# light_160mm_v1_0.net
KiCad netlist of a schematic drawn in EAGLE
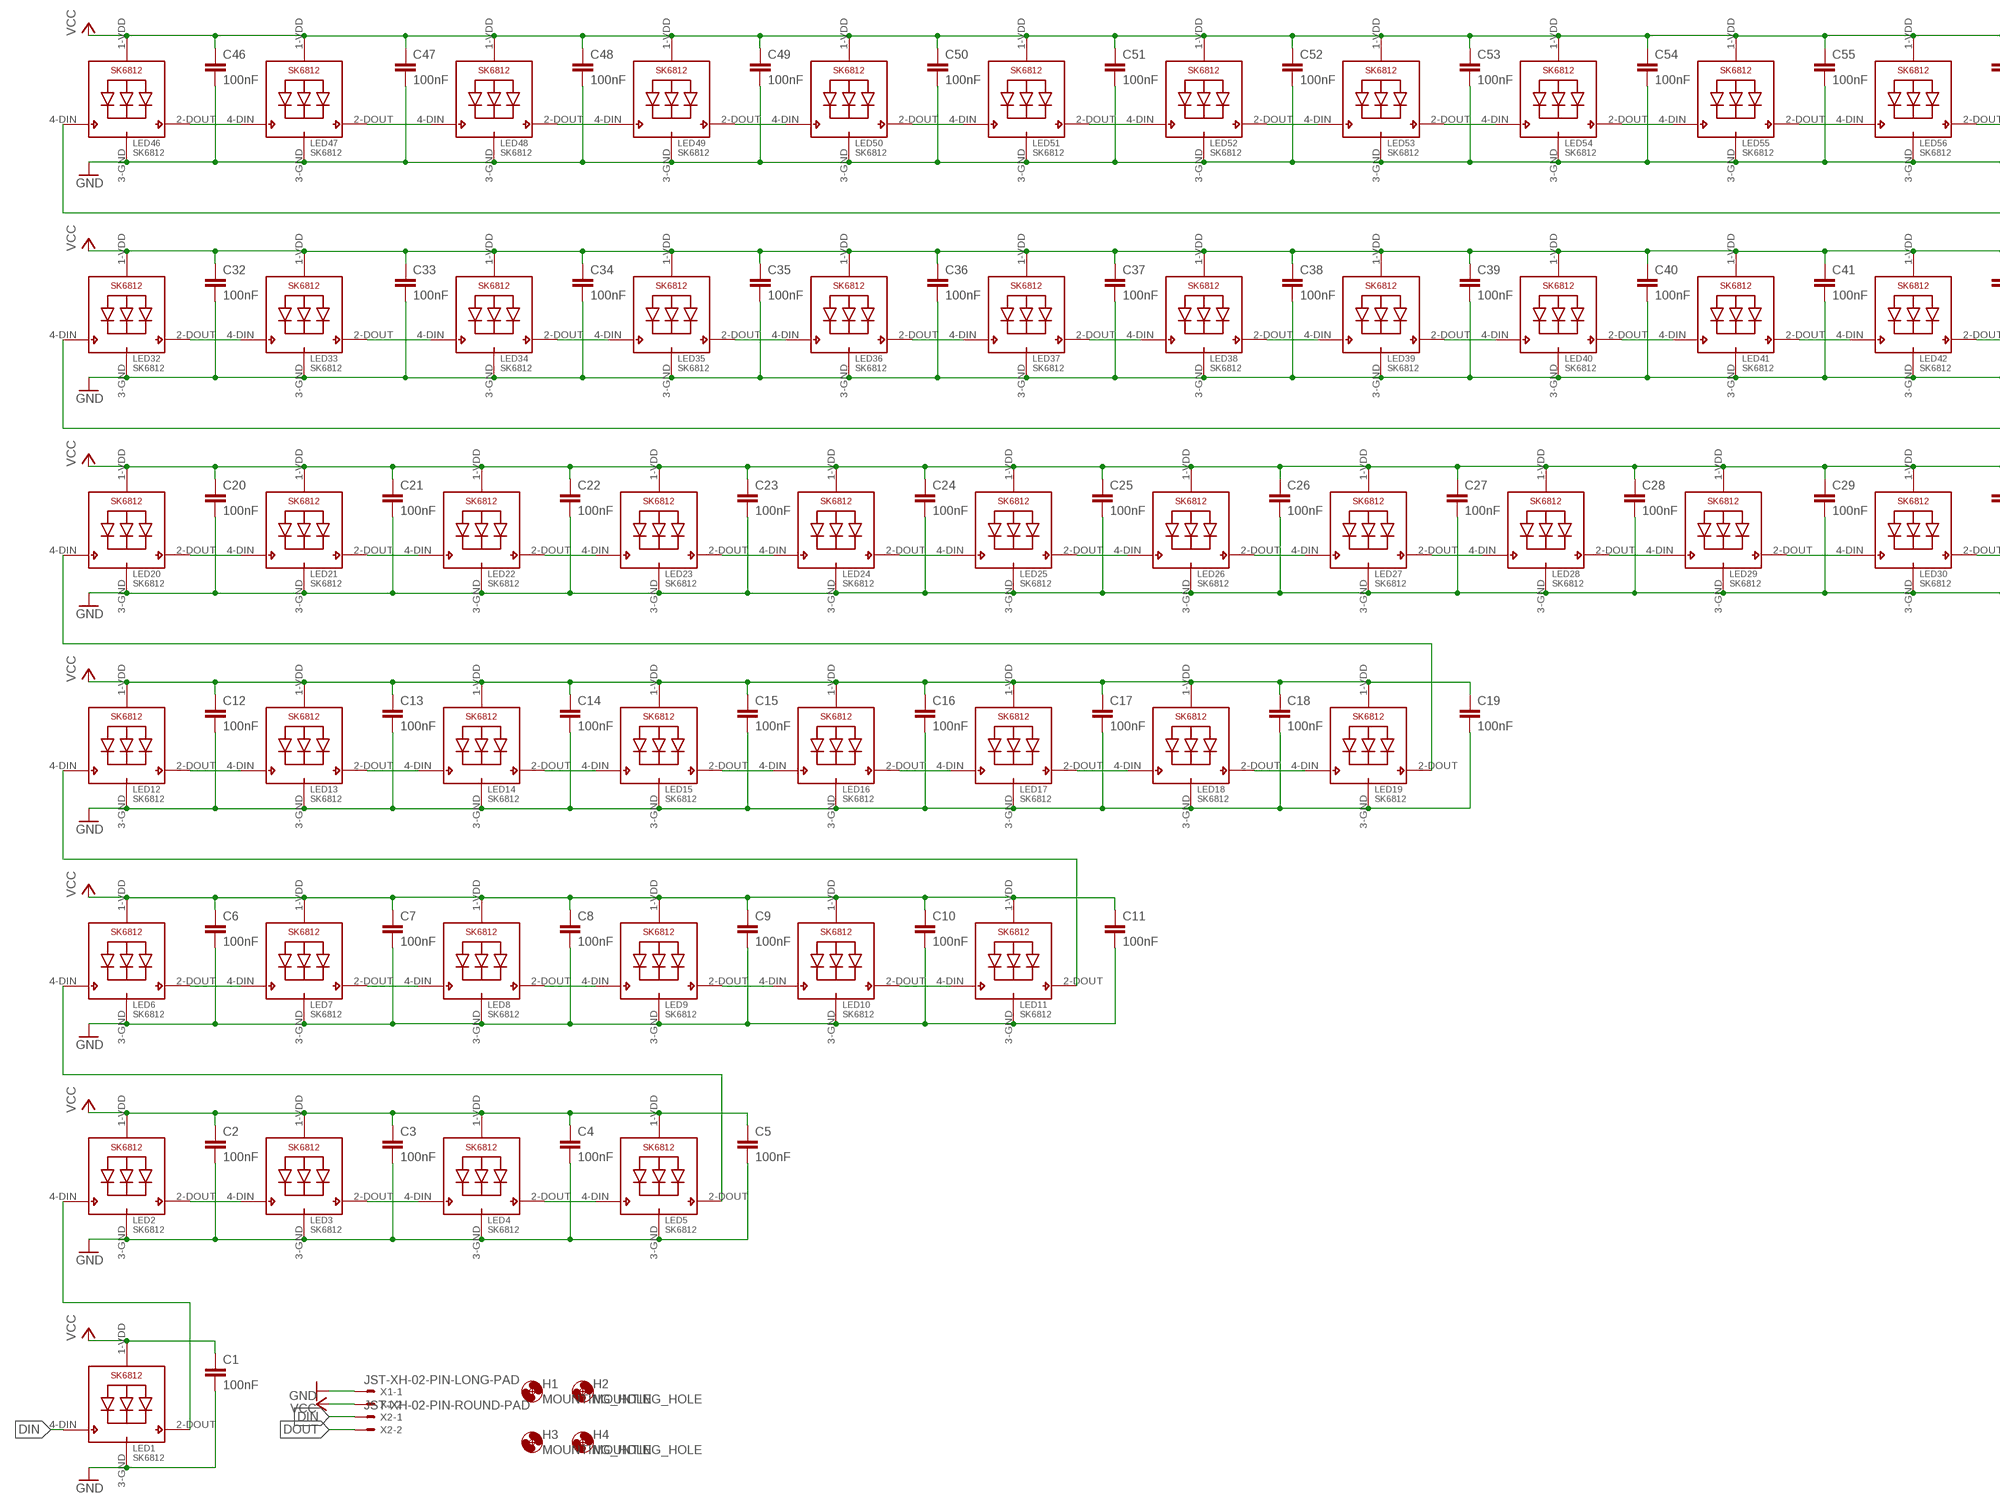
[diagram p0: schematic, sheet 1, part 1 of 2]
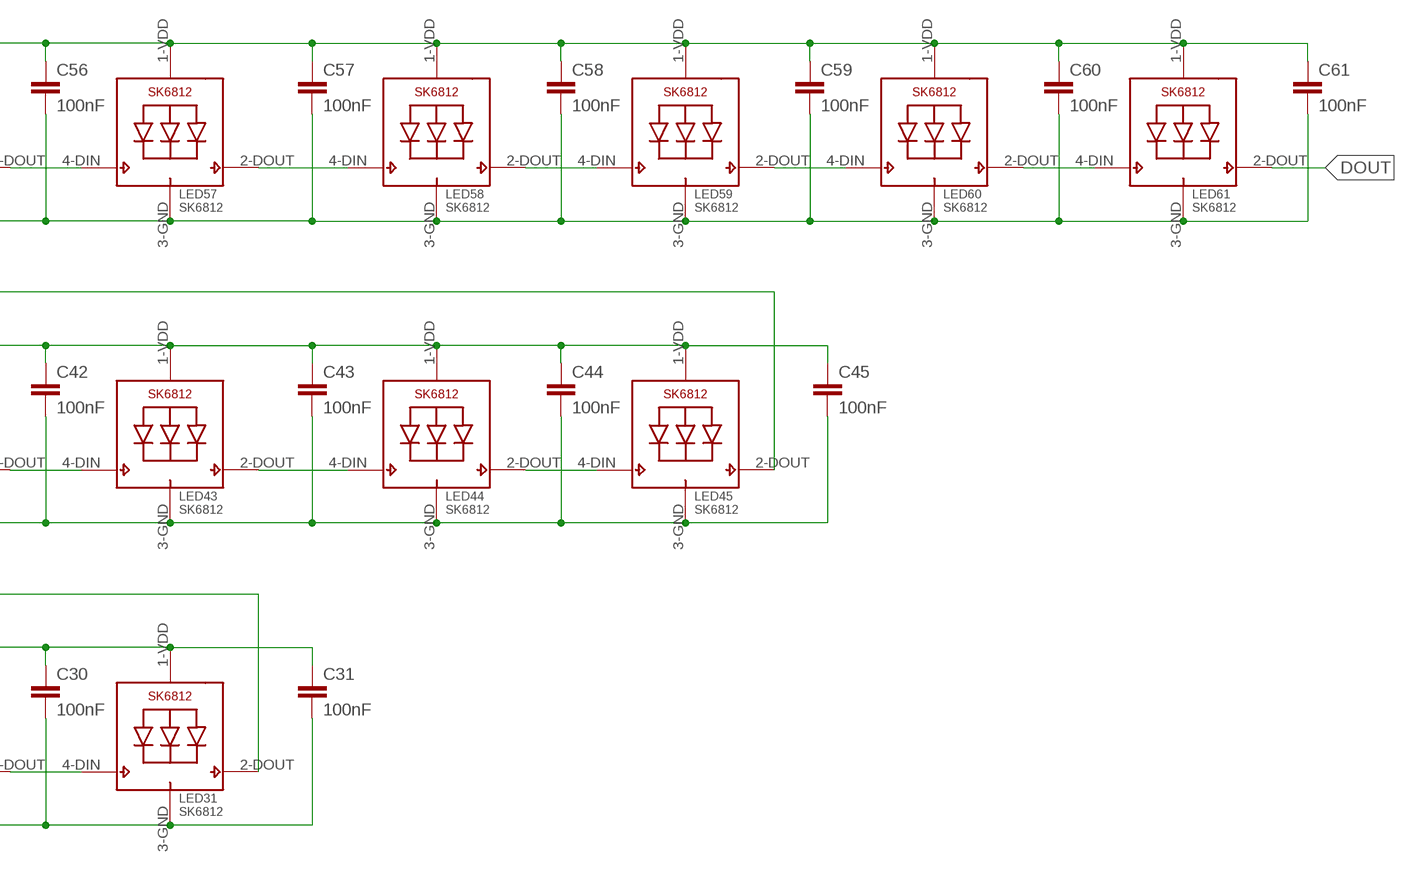
[diagram p1: schematic, sheet 1, part 2 of 2]

(export (version "E")
  (design (tool "Eeschema 10.0.6"))
  (components
    (comp (ref "C1")
      (value "100nF")
      (footprint "eagle-import:C0805")
      (libsource (lib "eagle-import") (part "C-EUC0805"))
    )
    (comp (ref "C2")
      (value "100nF")
      (footprint "eagle-import:C0805")
      (libsource (lib "eagle-import") (part "C-EUC0805"))
    )
    (comp (ref "C3")
      (value "100nF")
      (footprint "eagle-import:C0805")
      (libsource (lib "eagle-import") (part "C-EUC0805"))
    )
    (comp (ref "C4")
      (value "100nF")
      (footprint "eagle-import:C0805")
      (libsource (lib "eagle-import") (part "C-EUC0805"))
    )
    (comp (ref "C5")
      (value "100nF")
      (footprint "eagle-import:C0805")
      (libsource (lib "eagle-import") (part "C-EUC0805"))
    )
    (comp (ref "C6")
      (value "100nF")
      (footprint "eagle-import:C0805")
      (libsource (lib "eagle-import") (part "C-EUC0805"))
    )
    (comp (ref "C7")
      (value "100nF")
      (footprint "eagle-import:C0805")
      (libsource (lib "eagle-import") (part "C-EUC0805"))
    )
    (comp (ref "C8")
      (value "100nF")
      (footprint "eagle-import:C0805")
      (libsource (lib "eagle-import") (part "C-EUC0805"))
    )
    (comp (ref "C9")
      (value "100nF")
      (footprint "eagle-import:C0805")
      (libsource (lib "eagle-import") (part "C-EUC0805"))
    )
    (comp (ref "C10")
      (value "100nF")
      (footprint "eagle-import:C0805")
      (libsource (lib "eagle-import") (part "C-EUC0805"))
    )
    (comp (ref "C11")
      (value "100nF")
      (footprint "eagle-import:C0805")
      (libsource (lib "eagle-import") (part "C-EUC0805"))
    )
    (comp (ref "C12")
      (value "100nF")
      (footprint "eagle-import:C0805")
      (libsource (lib "eagle-import") (part "C-EUC0805"))
    )
    (comp (ref "C13")
      (value "100nF")
      (footprint "eagle-import:C0805")
      (libsource (lib "eagle-import") (part "C-EUC0805"))
    )
    (comp (ref "C14")
      (value "100nF")
      (footprint "eagle-import:C0805")
      (libsource (lib "eagle-import") (part "C-EUC0805"))
    )
    (comp (ref "C15")
      (value "100nF")
      (footprint "eagle-import:C0805")
      (libsource (lib "eagle-import") (part "C-EUC0805"))
    )
    (comp (ref "C16")
      (value "100nF")
      (footprint "eagle-import:C0805")
      (libsource (lib "eagle-import") (part "C-EUC0805"))
    )
    (comp (ref "C17")
      (value "100nF")
      (footprint "eagle-import:C0805")
      (libsource (lib "eagle-import") (part "C-EUC0805"))
    )
    (comp (ref "C18")
      (value "100nF")
      (footprint "eagle-import:C0805")
      (libsource (lib "eagle-import") (part "C-EUC0805"))
    )
    (comp (ref "C19")
      (value "100nF")
      (footprint "eagle-import:C0805")
      (libsource (lib "eagle-import") (part "C-EUC0805"))
    )
    (comp (ref "C20")
      (value "100nF")
      (footprint "eagle-import:C0805")
      (libsource (lib "eagle-import") (part "C-EUC0805"))
    )
    (comp (ref "C21")
      (value "100nF")
      (footprint "eagle-import:C0805")
      (libsource (lib "eagle-import") (part "C-EUC0805"))
    )
    (comp (ref "C22")
      (value "100nF")
      (footprint "eagle-import:C0805")
      (libsource (lib "eagle-import") (part "C-EUC0805"))
    )
    (comp (ref "C23")
      (value "100nF")
      (footprint "eagle-import:C0805")
      (libsource (lib "eagle-import") (part "C-EUC0805"))
    )
    (comp (ref "C24")
      (value "100nF")
      (footprint "eagle-import:C0805")
      (libsource (lib "eagle-import") (part "C-EUC0805"))
    )
    (comp (ref "C25")
      (value "100nF")
      (footprint "eagle-import:C0805")
      (libsource (lib "eagle-import") (part "C-EUC0805"))
    )
    (comp (ref "C26")
      (value "100nF")
      (footprint "eagle-import:C0805")
      (libsource (lib "eagle-import") (part "C-EUC0805"))
    )
    (comp (ref "C27")
      (value "100nF")
      (footprint "eagle-import:C0805")
      (libsource (lib "eagle-import") (part "C-EUC0805"))
    )
    (comp (ref "C28")
      (value "100nF")
      (footprint "eagle-import:C0805")
      (libsource (lib "eagle-import") (part "C-EUC0805"))
    )
    (comp (ref "C29")
      (value "100nF")
      (footprint "eagle-import:C0805")
      (libsource (lib "eagle-import") (part "C-EUC0805"))
    )
    (comp (ref "C30")
      (value "100nF")
      (footprint "eagle-import:C0805")
      (libsource (lib "eagle-import") (part "C-EUC0805"))
    )
    (comp (ref "C31")
      (value "100nF")
      (footprint "eagle-import:C0805")
      (libsource (lib "eagle-import") (part "C-EUC0805"))
    )
    (comp (ref "C32")
      (value "100nF")
      (footprint "eagle-import:C0805")
      (libsource (lib "eagle-import") (part "C-EUC0805"))
    )
    (comp (ref "C33")
      (value "100nF")
      (footprint "eagle-import:C0805")
      (libsource (lib "eagle-import") (part "C-EUC0805"))
    )
    (comp (ref "C34")
      (value "100nF")
      (footprint "eagle-import:C0805")
      (libsource (lib "eagle-import") (part "C-EUC0805"))
    )
    (comp (ref "C35")
      (value "100nF")
      (footprint "eagle-import:C0805")
      (libsource (lib "eagle-import") (part "C-EUC0805"))
    )
    (comp (ref "C36")
      (value "100nF")
      (footprint "eagle-import:C0805")
      (libsource (lib "eagle-import") (part "C-EUC0805"))
    )
    (comp (ref "C37")
      (value "100nF")
      (footprint "eagle-import:C0805")
      (libsource (lib "eagle-import") (part "C-EUC0805"))
    )
    (comp (ref "C38")
      (value "100nF")
      (footprint "eagle-import:C0805")
      (libsource (lib "eagle-import") (part "C-EUC0805"))
    )
    (comp (ref "C39")
      (value "100nF")
      (footprint "eagle-import:C0805")
      (libsource (lib "eagle-import") (part "C-EUC0805"))
    )
    (comp (ref "C40")
      (value "100nF")
      (footprint "eagle-import:C0805")
      (libsource (lib "eagle-import") (part "C-EUC0805"))
    )
    (comp (ref "C41")
      (value "100nF")
      (footprint "eagle-import:C0805")
      (libsource (lib "eagle-import") (part "C-EUC0805"))
    )
    (comp (ref "C42")
      (value "100nF")
      (footprint "eagle-import:C0805")
      (libsource (lib "eagle-import") (part "C-EUC0805"))
    )
    (comp (ref "C43")
      (value "100nF")
      (footprint "eagle-import:C0805")
      (libsource (lib "eagle-import") (part "C-EUC0805"))
    )
    (comp (ref "C44")
      (value "100nF")
      (footprint "eagle-import:C0805")
      (libsource (lib "eagle-import") (part "C-EUC0805"))
    )
    (comp (ref "C45")
      (value "100nF")
      (footprint "eagle-import:C0805")
      (libsource (lib "eagle-import") (part "C-EUC0805"))
    )
    (comp (ref "C46")
      (value "100nF")
      (footprint "eagle-import:C0805")
      (libsource (lib "eagle-import") (part "C-EUC0805"))
    )
    (comp (ref "C47")
      (value "100nF")
      (footprint "eagle-import:C0805")
      (libsource (lib "eagle-import") (part "C-EUC0805"))
    )
    (comp (ref "C48")
      (value "100nF")
      (footprint "eagle-import:C0805")
      (libsource (lib "eagle-import") (part "C-EUC0805"))
    )
    (comp (ref "C49")
      (value "100nF")
      (footprint "eagle-import:C0805")
      (libsource (lib "eagle-import") (part "C-EUC0805"))
    )
    (comp (ref "C50")
      (value "100nF")
      (footprint "eagle-import:C0805")
      (libsource (lib "eagle-import") (part "C-EUC0805"))
    )
    (comp (ref "C51")
      (value "100nF")
      (footprint "eagle-import:C0805")
      (libsource (lib "eagle-import") (part "C-EUC0805"))
    )
    (comp (ref "C52")
      (value "100nF")
      (footprint "eagle-import:C0805")
      (libsource (lib "eagle-import") (part "C-EUC0805"))
    )
    (comp (ref "C53")
      (value "100nF")
      (footprint "eagle-import:C0805")
      (libsource (lib "eagle-import") (part "C-EUC0805"))
    )
    (comp (ref "C54")
      (value "100nF")
      (footprint "eagle-import:C0805")
      (libsource (lib "eagle-import") (part "C-EUC0805"))
    )
    (comp (ref "C55")
      (value "100nF")
      (footprint "eagle-import:C0805")
      (libsource (lib "eagle-import") (part "C-EUC0805"))
    )
    (comp (ref "C56")
      (value "100nF")
      (footprint "eagle-import:C0805")
      (libsource (lib "eagle-import") (part "C-EUC0805"))
    )
    (comp (ref "C57")
      (value "100nF")
      (footprint "eagle-import:C0805")
      (libsource (lib "eagle-import") (part "C-EUC0805"))
    )
    (comp (ref "C58")
      (value "100nF")
      (footprint "eagle-import:C0805")
      (libsource (lib "eagle-import") (part "C-EUC0805"))
    )
    (comp (ref "C59")
      (value "100nF")
      (footprint "eagle-import:C0805")
      (libsource (lib "eagle-import") (part "C-EUC0805"))
    )
    (comp (ref "C60")
      (value "100nF")
      (footprint "eagle-import:C0805")
      (libsource (lib "eagle-import") (part "C-EUC0805"))
    )
    (comp (ref "C61")
      (value "100nF")
      (footprint "eagle-import:C0805")
      (libsource (lib "eagle-import") (part "C-EUC0805"))
    )
    (comp (ref "H1")
      (value "MOUNTING_HOLE")
      (footprint "eagle-import:4,1")
      (libsource (lib "eagle-import") (part "MOUNTING_HOLE"))
    )
    (comp (ref "H2")
      (value "MOUNTING_HOLE")
      (footprint "eagle-import:4,1")
      (libsource (lib "eagle-import") (part "MOUNTING_HOLE"))
    )
    (comp (ref "H3")
      (value "MOUNTING_HOLE")
      (footprint "eagle-import:4,1")
      (libsource (lib "eagle-import") (part "MOUNTING_HOLE"))
    )
    (comp (ref "H4")
      (value "MOUNTING_HOLE")
      (footprint "eagle-import:4,1")
      (libsource (lib "eagle-import") (part "MOUNTING_HOLE"))
    )
    (comp (ref "LED1")
      (value "SK6812")
      (footprint "eagle-import:LED5050")
      (libsource (lib "eagle-import") (part "SK6812_5050"))
    )
    (comp (ref "LED2")
      (value "SK6812")
      (footprint "eagle-import:LED5050")
      (libsource (lib "eagle-import") (part "SK6812_5050"))
    )
    (comp (ref "LED3")
      (value "SK6812")
      (footprint "eagle-import:LED5050")
      (libsource (lib "eagle-import") (part "SK6812_5050"))
    )
    (comp (ref "LED4")
      (value "SK6812")
      (footprint "eagle-import:LED5050")
      (libsource (lib "eagle-import") (part "SK6812_5050"))
    )
    (comp (ref "LED5")
      (value "SK6812")
      (footprint "eagle-import:LED5050")
      (libsource (lib "eagle-import") (part "SK6812_5050"))
    )
    (comp (ref "LED6")
      (value "SK6812")
      (footprint "eagle-import:LED5050")
      (libsource (lib "eagle-import") (part "SK6812_5050"))
    )
    (comp (ref "LED7")
      (value "SK6812")
      (footprint "eagle-import:LED5050")
      (libsource (lib "eagle-import") (part "SK6812_5050"))
    )
    (comp (ref "LED8")
      (value "SK6812")
      (footprint "eagle-import:LED5050")
      (libsource (lib "eagle-import") (part "SK6812_5050"))
    )
    (comp (ref "LED9")
      (value "SK6812")
      (footprint "eagle-import:LED5050")
      (libsource (lib "eagle-import") (part "SK6812_5050"))
    )
    (comp (ref "LED10")
      (value "SK6812")
      (footprint "eagle-import:LED5050")
      (libsource (lib "eagle-import") (part "SK6812_5050"))
    )
    (comp (ref "LED11")
      (value "SK6812")
      (footprint "eagle-import:LED5050")
      (libsource (lib "eagle-import") (part "SK6812_5050"))
    )
    (comp (ref "LED12")
      (value "SK6812")
      (footprint "eagle-import:LED5050")
      (libsource (lib "eagle-import") (part "SK6812_5050"))
    )
    (comp (ref "LED13")
      (value "SK6812")
      (footprint "eagle-import:LED5050")
      (libsource (lib "eagle-import") (part "SK6812_5050"))
    )
    (comp (ref "LED14")
      (value "SK6812")
      (footprint "eagle-import:LED5050")
      (libsource (lib "eagle-import") (part "SK6812_5050"))
    )
    (comp (ref "LED15")
      (value "SK6812")
      (footprint "eagle-import:LED5050")
      (libsource (lib "eagle-import") (part "SK6812_5050"))
    )
    (comp (ref "LED16")
      (value "SK6812")
      (footprint "eagle-import:LED5050")
      (libsource (lib "eagle-import") (part "SK6812_5050"))
    )
    (comp (ref "LED17")
      (value "SK6812")
      (footprint "eagle-import:LED5050")
      (libsource (lib "eagle-import") (part "SK6812_5050"))
    )
    (comp (ref "LED18")
      (value "SK6812")
      (footprint "eagle-import:LED5050")
      (libsource (lib "eagle-import") (part "SK6812_5050"))
    )
    (comp (ref "LED19")
      (value "SK6812")
      (footprint "eagle-import:LED5050")
      (libsource (lib "eagle-import") (part "SK6812_5050"))
    )
    (comp (ref "LED20")
      (value "SK6812")
      (footprint "eagle-import:LED5050")
      (libsource (lib "eagle-import") (part "SK6812_5050"))
    )
    (comp (ref "LED21")
      (value "SK6812")
      (footprint "eagle-import:LED5050")
      (libsource (lib "eagle-import") (part "SK6812_5050"))
    )
    (comp (ref "LED22")
      (value "SK6812")
      (footprint "eagle-import:LED5050")
      (libsource (lib "eagle-import") (part "SK6812_5050"))
    )
    (comp (ref "LED23")
      (value "SK6812")
      (footprint "eagle-import:LED5050")
      (libsource (lib "eagle-import") (part "SK6812_5050"))
    )
    (comp (ref "LED24")
      (value "SK6812")
      (footprint "eagle-import:LED5050")
      (libsource (lib "eagle-import") (part "SK6812_5050"))
    )
    (comp (ref "LED25")
      (value "SK6812")
      (footprint "eagle-import:LED5050")
      (libsource (lib "eagle-import") (part "SK6812_5050"))
    )
    (comp (ref "LED26")
      (value "SK6812")
      (footprint "eagle-import:LED5050")
      (libsource (lib "eagle-import") (part "SK6812_5050"))
    )
    (comp (ref "LED27")
      (value "SK6812")
      (footprint "eagle-import:LED5050")
      (libsource (lib "eagle-import") (part "SK6812_5050"))
    )
    (comp (ref "LED28")
      (value "SK6812")
      (footprint "eagle-import:LED5050")
      (libsource (lib "eagle-import") (part "SK6812_5050"))
    )
    (comp (ref "LED29")
      (value "SK6812")
      (footprint "eagle-import:LED5050")
      (libsource (lib "eagle-import") (part "SK6812_5050"))
    )
    (comp (ref "LED30")
      (value "SK6812")
      (footprint "eagle-import:LED5050")
      (libsource (lib "eagle-import") (part "SK6812_5050"))
    )
    (comp (ref "LED31")
      (value "SK6812")
      (footprint "eagle-import:LED5050")
      (libsource (lib "eagle-import") (part "SK6812_5050"))
    )
    (comp (ref "LED32")
      (value "SK6812")
      (footprint "eagle-import:LED5050")
      (libsource (lib "eagle-import") (part "SK6812_5050"))
    )
    (comp (ref "LED33")
      (value "SK6812")
      (footprint "eagle-import:LED5050")
      (libsource (lib "eagle-import") (part "SK6812_5050"))
    )
    (comp (ref "LED34")
      (value "SK6812")
      (footprint "eagle-import:LED5050")
      (libsource (lib "eagle-import") (part "SK6812_5050"))
    )
    (comp (ref "LED35")
      (value "SK6812")
      (footprint "eagle-import:LED5050")
      (libsource (lib "eagle-import") (part "SK6812_5050"))
    )
    (comp (ref "LED36")
      (value "SK6812")
      (footprint "eagle-import:LED5050")
      (libsource (lib "eagle-import") (part "SK6812_5050"))
    )
    (comp (ref "LED37")
      (value "SK6812")
      (footprint "eagle-import:LED5050")
      (libsource (lib "eagle-import") (part "SK6812_5050"))
    )
    (comp (ref "LED38")
      (value "SK6812")
      (footprint "eagle-import:LED5050")
      (libsource (lib "eagle-import") (part "SK6812_5050"))
    )
    (comp (ref "LED39")
      (value "SK6812")
      (footprint "eagle-import:LED5050")
      (libsource (lib "eagle-import") (part "SK6812_5050"))
    )
    (comp (ref "LED40")
      (value "SK6812")
      (footprint "eagle-import:LED5050")
      (libsource (lib "eagle-import") (part "SK6812_5050"))
    )
    (comp (ref "LED41")
      (value "SK6812")
      (footprint "eagle-import:LED5050")
      (libsource (lib "eagle-import") (part "SK6812_5050"))
    )
    (comp (ref "LED42")
      (value "SK6812")
      (footprint "eagle-import:LED5050")
      (libsource (lib "eagle-import") (part "SK6812_5050"))
    )
    (comp (ref "LED43")
      (value "SK6812")
      (footprint "eagle-import:LED5050")
      (libsource (lib "eagle-import") (part "SK6812_5050"))
    )
    (comp (ref "LED44")
      (value "SK6812")
      (footprint "eagle-import:LED5050")
      (libsource (lib "eagle-import") (part "SK6812_5050"))
    )
    (comp (ref "LED45")
      (value "SK6812")
      (footprint "eagle-import:LED5050")
      (libsource (lib "eagle-import") (part "SK6812_5050"))
    )
    (comp (ref "LED46")
      (value "SK6812")
      (footprint "eagle-import:LED5050")
      (libsource (lib "eagle-import") (part "SK6812_5050"))
    )
    (comp (ref "LED47")
      (value "SK6812")
      (footprint "eagle-import:LED5050")
      (libsource (lib "eagle-import") (part "SK6812_5050"))
    )
    (comp (ref "LED48")
      (value "SK6812")
      (footprint "eagle-import:LED5050")
      (libsource (lib "eagle-import") (part "SK6812_5050"))
    )
    (comp (ref "LED49")
      (value "SK6812")
      (footprint "eagle-import:LED5050")
      (libsource (lib "eagle-import") (part "SK6812_5050"))
    )
    (comp (ref "LED50")
      (value "SK6812")
      (footprint "eagle-import:LED5050")
      (libsource (lib "eagle-import") (part "SK6812_5050"))
    )
    (comp (ref "LED51")
      (value "SK6812")
      (footprint "eagle-import:LED5050")
      (libsource (lib "eagle-import") (part "SK6812_5050"))
    )
    (comp (ref "LED52")
      (value "SK6812")
      (footprint "eagle-import:LED5050")
      (libsource (lib "eagle-import") (part "SK6812_5050"))
    )
    (comp (ref "LED53")
      (value "SK6812")
      (footprint "eagle-import:LED5050")
      (libsource (lib "eagle-import") (part "SK6812_5050"))
    )
    (comp (ref "LED54")
      (value "SK6812")
      (footprint "eagle-import:LED5050")
      (libsource (lib "eagle-import") (part "SK6812_5050"))
    )
    (comp (ref "LED55")
      (value "SK6812")
      (footprint "eagle-import:LED5050")
      (libsource (lib "eagle-import") (part "SK6812_5050"))
    )
    (comp (ref "LED56")
      (value "SK6812")
      (footprint "eagle-import:LED5050")
      (libsource (lib "eagle-import") (part "SK6812_5050"))
    )
    (comp (ref "LED57")
      (value "SK6812")
      (footprint "eagle-import:LED5050")
      (libsource (lib "eagle-import") (part "SK6812_5050"))
    )
    (comp (ref "LED58")
      (value "SK6812")
      (footprint "eagle-import:LED5050")
      (libsource (lib "eagle-import") (part "SK6812_5050"))
    )
    (comp (ref "LED59")
      (value "SK6812")
      (footprint "eagle-import:LED5050")
      (libsource (lib "eagle-import") (part "SK6812_5050"))
    )
    (comp (ref "LED60")
      (value "SK6812")
      (footprint "eagle-import:LED5050")
      (libsource (lib "eagle-import") (part "SK6812_5050"))
    )
    (comp (ref "LED61")
      (value "SK6812")
      (footprint "eagle-import:LED5050")
      (libsource (lib "eagle-import") (part "SK6812_5050"))
    )
    (comp (ref "X1")
      (value "JST-XH-02-PIN-LONG-PAD")
      (footprint "eagle-import:JST-XH-02-PACKAGE-LONG-PAD")
      (libsource (lib "eagle-import") (part "JST-XH-02-PIN-LONG-PAD"))
    )
    (comp (ref "X2")
      (value "JST-XH-02-PIN-ROUND-PAD")
      (footprint "eagle-import:JST-XH-02-PACKAGE-ROUND-PAD")
      (libsource (lib "eagle-import") (part "JST-XH-02-PIN-ROUND-PAD"))
    )
  )
  (nets
    (net (code "1") (name "DIN") (class "Default")
      (node (ref "LED1") (pin "4-DIN") (pinfunction "DI_4-DIN") (pintype "input"))
      (node (ref "X2") (pin "1") (pinfunction "S_1") (pintype "passive"))
    )
    (net (code "2") (name "DOUT") (class "Default")
      (node (ref "LED61") (pin "2-DOUT") (pinfunction "DO_2-DOUT") (pintype "output"))
      (node (ref "X2") (pin "2") (pinfunction "S_2") (pintype "passive"))
    )
    (net (code "3") (name "GND") (class "Default")
      (node (ref "C1") (pin "2") (pinfunction "2_2") (pintype "passive"))
      (node (ref "C10") (pin "2") (pinfunction "2_2") (pintype "passive"))
      (node (ref "C11") (pin "2") (pinfunction "2_2") (pintype "passive"))
      (node (ref "C12") (pin "2") (pinfunction "2_2") (pintype "passive"))
      (node (ref "C13") (pin "2") (pinfunction "2_2") (pintype "passive"))
      (node (ref "C14") (pin "2") (pinfunction "2_2") (pintype "passive"))
      (node (ref "C15") (pin "2") (pinfunction "2_2") (pintype "passive"))
      (node (ref "C16") (pin "2") (pinfunction "2_2") (pintype "passive"))
      (node (ref "C17") (pin "2") (pinfunction "2_2") (pintype "passive"))
      (node (ref "C18") (pin "2") (pinfunction "2_2") (pintype "passive"))
      (node (ref "C19") (pin "2") (pinfunction "2_2") (pintype "passive"))
      (node (ref "C2") (pin "2") (pinfunction "2_2") (pintype "passive"))
      (node (ref "C20") (pin "2") (pinfunction "2_2") (pintype "passive"))
      (node (ref "C21") (pin "2") (pinfunction "2_2") (pintype "passive"))
      (node (ref "C22") (pin "2") (pinfunction "2_2") (pintype "passive"))
      (node (ref "C23") (pin "2") (pinfunction "2_2") (pintype "passive"))
      (node (ref "C24") (pin "2") (pinfunction "2_2") (pintype "passive"))
      (node (ref "C25") (pin "2") (pinfunction "2_2") (pintype "passive"))
      (node (ref "C26") (pin "2") (pinfunction "2_2") (pintype "passive"))
      (node (ref "C27") (pin "2") (pinfunction "2_2") (pintype "passive"))
      (node (ref "C28") (pin "2") (pinfunction "2_2") (pintype "passive"))
      (node (ref "C29") (pin "2") (pinfunction "2_2") (pintype "passive"))
      (node (ref "C3") (pin "2") (pinfunction "2_2") (pintype "passive"))
      (node (ref "C30") (pin "2") (pinfunction "2_2") (pintype "passive"))
      (node (ref "C31") (pin "2") (pinfunction "2_2") (pintype "passive"))
      (node (ref "C32") (pin "2") (pinfunction "2_2") (pintype "passive"))
      (node (ref "C33") (pin "2") (pinfunction "2_2") (pintype "passive"))
      (node (ref "C34") (pin "2") (pinfunction "2_2") (pintype "passive"))
      (node (ref "C35") (pin "2") (pinfunction "2_2") (pintype "passive"))
      (node (ref "C36") (pin "2") (pinfunction "2_2") (pintype "passive"))
      (node (ref "C37") (pin "2") (pinfunction "2_2") (pintype "passive"))
      (node (ref "C38") (pin "2") (pinfunction "2_2") (pintype "passive"))
      (node (ref "C39") (pin "2") (pinfunction "2_2") (pintype "passive"))
      (node (ref "C4") (pin "2") (pinfunction "2_2") (pintype "passive"))
      (node (ref "C40") (pin "2") (pinfunction "2_2") (pintype "passive"))
      (node (ref "C41") (pin "2") (pinfunction "2_2") (pintype "passive"))
      (node (ref "C42") (pin "2") (pinfunction "2_2") (pintype "passive"))
      (node (ref "C43") (pin "2") (pinfunction "2_2") (pintype "passive"))
      (node (ref "C44") (pin "2") (pinfunction "2_2") (pintype "passive"))
      (node (ref "C45") (pin "2") (pinfunction "2_2") (pintype "passive"))
      (node (ref "C46") (pin "2") (pinfunction "2_2") (pintype "passive"))
      (node (ref "C47") (pin "2") (pinfunction "2_2") (pintype "passive"))
      (node (ref "C48") (pin "2") (pinfunction "2_2") (pintype "passive"))
      (node (ref "C49") (pin "2") (pinfunction "2_2") (pintype "passive"))
      (node (ref "C5") (pin "2") (pinfunction "2_2") (pintype "passive"))
      (node (ref "C50") (pin "2") (pinfunction "2_2") (pintype "passive"))
      (node (ref "C51") (pin "2") (pinfunction "2_2") (pintype "passive"))
      (node (ref "C52") (pin "2") (pinfunction "2_2") (pintype "passive"))
      (node (ref "C53") (pin "2") (pinfunction "2_2") (pintype "passive"))
      (node (ref "C54") (pin "2") (pinfunction "2_2") (pintype "passive"))
      (node (ref "C55") (pin "2") (pinfunction "2_2") (pintype "passive"))
      (node (ref "C56") (pin "2") (pinfunction "2_2") (pintype "passive"))
      (node (ref "C57") (pin "2") (pinfunction "2_2") (pintype "passive"))
      (node (ref "C58") (pin "2") (pinfunction "2_2") (pintype "passive"))
      (node (ref "C59") (pin "2") (pinfunction "2_2") (pintype "passive"))
      (node (ref "C6") (pin "2") (pinfunction "2_2") (pintype "passive"))
      (node (ref "C60") (pin "2") (pinfunction "2_2") (pintype "passive"))
      (node (ref "C61") (pin "2") (pinfunction "2_2") (pintype "passive"))
      (node (ref "C7") (pin "2") (pinfunction "2_2") (pintype "passive"))
      (node (ref "C8") (pin "2") (pinfunction "2_2") (pintype "passive"))
      (node (ref "C9") (pin "2") (pinfunction "2_2") (pintype "passive"))
      (node (ref "LED1") (pin "3-GND") (pinfunction "GND_3-GND") (pintype "power_in"))
      (node (ref "LED10") (pin "3-GND") (pinfunction "GND_3-GND") (pintype "power_in"))
      (node (ref "LED11") (pin "3-GND") (pinfunction "GND_3-GND") (pintype "power_in"))
      (node (ref "LED12") (pin "3-GND") (pinfunction "GND_3-GND") (pintype "power_in"))
      (node (ref "LED13") (pin "3-GND") (pinfunction "GND_3-GND") (pintype "power_in"))
      (node (ref "LED14") (pin "3-GND") (pinfunction "GND_3-GND") (pintype "power_in"))
      (node (ref "LED15") (pin "3-GND") (pinfunction "GND_3-GND") (pintype "power_in"))
      (node (ref "LED16") (pin "3-GND") (pinfunction "GND_3-GND") (pintype "power_in"))
      (node (ref "LED17") (pin "3-GND") (pinfunction "GND_3-GND") (pintype "power_in"))
      (node (ref "LED18") (pin "3-GND") (pinfunction "GND_3-GND") (pintype "power_in"))
      (node (ref "LED19") (pin "3-GND") (pinfunction "GND_3-GND") (pintype "power_in"))
      (node (ref "LED2") (pin "3-GND") (pinfunction "GND_3-GND") (pintype "power_in"))
      (node (ref "LED20") (pin "3-GND") (pinfunction "GND_3-GND") (pintype "power_in"))
      (node (ref "LED21") (pin "3-GND") (pinfunction "GND_3-GND") (pintype "power_in"))
      (node (ref "LED22") (pin "3-GND") (pinfunction "GND_3-GND") (pintype "power_in"))
      (node (ref "LED23") (pin "3-GND") (pinfunction "GND_3-GND") (pintype "power_in"))
      (node (ref "LED24") (pin "3-GND") (pinfunction "GND_3-GND") (pintype "power_in"))
      (node (ref "LED25") (pin "3-GND") (pinfunction "GND_3-GND") (pintype "power_in"))
      (node (ref "LED26") (pin "3-GND") (pinfunction "GND_3-GND") (pintype "power_in"))
      (node (ref "LED27") (pin "3-GND") (pinfunction "GND_3-GND") (pintype "power_in"))
      (node (ref "LED28") (pin "3-GND") (pinfunction "GND_3-GND") (pintype "power_in"))
      (node (ref "LED29") (pin "3-GND") (pinfunction "GND_3-GND") (pintype "power_in"))
      (node (ref "LED3") (pin "3-GND") (pinfunction "GND_3-GND") (pintype "power_in"))
      (node (ref "LED30") (pin "3-GND") (pinfunction "GND_3-GND") (pintype "power_in"))
      (node (ref "LED31") (pin "3-GND") (pinfunction "GND_3-GND") (pintype "power_in"))
      (node (ref "LED32") (pin "3-GND") (pinfunction "GND_3-GND") (pintype "power_in"))
      (node (ref "LED33") (pin "3-GND") (pinfunction "GND_3-GND") (pintype "power_in"))
      (node (ref "LED34") (pin "3-GND") (pinfunction "GND_3-GND") (pintype "power_in"))
      (node (ref "LED35") (pin "3-GND") (pinfunction "GND_3-GND") (pintype "power_in"))
      (node (ref "LED36") (pin "3-GND") (pinfunction "GND_3-GND") (pintype "power_in"))
      (node (ref "LED37") (pin "3-GND") (pinfunction "GND_3-GND") (pintype "power_in"))
      (node (ref "LED38") (pin "3-GND") (pinfunction "GND_3-GND") (pintype "power_in"))
      (node (ref "LED39") (pin "3-GND") (pinfunction "GND_3-GND") (pintype "power_in"))
      (node (ref "LED4") (pin "3-GND") (pinfunction "GND_3-GND") (pintype "power_in"))
      (node (ref "LED40") (pin "3-GND") (pinfunction "GND_3-GND") (pintype "power_in"))
      (node (ref "LED41") (pin "3-GND") (pinfunction "GND_3-GND") (pintype "power_in"))
      (node (ref "LED42") (pin "3-GND") (pinfunction "GND_3-GND") (pintype "power_in"))
      (node (ref "LED43") (pin "3-GND") (pinfunction "GND_3-GND") (pintype "power_in"))
      (node (ref "LED44") (pin "3-GND") (pinfunction "GND_3-GND") (pintype "power_in"))
      (node (ref "LED45") (pin "3-GND") (pinfunction "GND_3-GND") (pintype "power_in"))
      (node (ref "LED46") (pin "3-GND") (pinfunction "GND_3-GND") (pintype "power_in"))
      (node (ref "LED47") (pin "3-GND") (pinfunction "GND_3-GND") (pintype "power_in"))
      (node (ref "LED48") (pin "3-GND") (pinfunction "GND_3-GND") (pintype "power_in"))
      (node (ref "LED49") (pin "3-GND") (pinfunction "GND_3-GND") (pintype "power_in"))
      (node (ref "LED5") (pin "3-GND") (pinfunction "GND_3-GND") (pintype "power_in"))
      (node (ref "LED50") (pin "3-GND") (pinfunction "GND_3-GND") (pintype "power_in"))
      (node (ref "LED51") (pin "3-GND") (pinfunction "GND_3-GND") (pintype "power_in"))
      (node (ref "LED52") (pin "3-GND") (pinfunction "GND_3-GND") (pintype "power_in"))
      (node (ref "LED53") (pin "3-GND") (pinfunction "GND_3-GND") (pintype "power_in"))
      (node (ref "LED54") (pin "3-GND") (pinfunction "GND_3-GND") (pintype "power_in"))
      (node (ref "LED55") (pin "3-GND") (pinfunction "GND_3-GND") (pintype "power_in"))
      (node (ref "LED56") (pin "3-GND") (pinfunction "GND_3-GND") (pintype "power_in"))
      (node (ref "LED57") (pin "3-GND") (pinfunction "GND_3-GND") (pintype "power_in"))
      (node (ref "LED58") (pin "3-GND") (pinfunction "GND_3-GND") (pintype "power_in"))
      (node (ref "LED59") (pin "3-GND") (pinfunction "GND_3-GND") (pintype "power_in"))
      (node (ref "LED6") (pin "3-GND") (pinfunction "GND_3-GND") (pintype "power_in"))
      (node (ref "LED60") (pin "3-GND") (pinfunction "GND_3-GND") (pintype "power_in"))
      (node (ref "LED61") (pin "3-GND") (pinfunction "GND_3-GND") (pintype "power_in"))
      (node (ref "LED7") (pin "3-GND") (pinfunction "GND_3-GND") (pintype "power_in"))
      (node (ref "LED8") (pin "3-GND") (pinfunction "GND_3-GND") (pintype "power_in"))
      (node (ref "LED9") (pin "3-GND") (pinfunction "GND_3-GND") (pintype "power_in"))
      (node (ref "X1") (pin "1") (pinfunction "S_1") (pintype "passive"))
    )
    (net (code "4") (name "Net-(LED1-DO)") (class "Default")
      (node (ref "LED1") (pin "2-DOUT") (pinfunction "DO_2-DOUT") (pintype "output"))
      (node (ref "LED2") (pin "4-DIN") (pinfunction "DI_4-DIN") (pintype "input"))
    )
    (net (code "5") (name "Net-(LED2-DO)") (class "Default")
      (node (ref "LED2") (pin "2-DOUT") (pinfunction "DO_2-DOUT") (pintype "output"))
      (node (ref "LED3") (pin "4-DIN") (pinfunction "DI_4-DIN") (pintype "input"))
    )
    (net (code "6") (name "Net-(LED3-DO)") (class "Default")
      (node (ref "LED3") (pin "2-DOUT") (pinfunction "DO_2-DOUT") (pintype "output"))
      (node (ref "LED4") (pin "4-DIN") (pinfunction "DI_4-DIN") (pintype "input"))
    )
    (net (code "7") (name "Net-(LED4-DO)") (class "Default")
      (node (ref "LED4") (pin "2-DOUT") (pinfunction "DO_2-DOUT") (pintype "output"))
      (node (ref "LED5") (pin "4-DIN") (pinfunction "DI_4-DIN") (pintype "input"))
    )
    (net (code "8") (name "Net-(LED5-DO)") (class "Default")
      (node (ref "LED5") (pin "2-DOUT") (pinfunction "DO_2-DOUT") (pintype "output"))
      (node (ref "LED6") (pin "4-DIN") (pinfunction "DI_4-DIN") (pintype "input"))
    )
    (net (code "9") (name "Net-(LED6-DO)") (class "Default")
      (node (ref "LED6") (pin "2-DOUT") (pinfunction "DO_2-DOUT") (pintype "output"))
      (node (ref "LED7") (pin "4-DIN") (pinfunction "DI_4-DIN") (pintype "input"))
    )
    (net (code "10") (name "Net-(LED7-DO)") (class "Default")
      (node (ref "LED7") (pin "2-DOUT") (pinfunction "DO_2-DOUT") (pintype "output"))
      (node (ref "LED8") (pin "4-DIN") (pinfunction "DI_4-DIN") (pintype "input"))
    )
    (net (code "11") (name "Net-(LED8-DO)") (class "Default")
      (node (ref "LED8") (pin "2-DOUT") (pinfunction "DO_2-DOUT") (pintype "output"))
      (node (ref "LED9") (pin "4-DIN") (pinfunction "DI_4-DIN") (pintype "input"))
    )
    (net (code "12") (name "Net-(LED10-DI)") (class "Default")
      (node (ref "LED10") (pin "4-DIN") (pinfunction "DI_4-DIN") (pintype "input"))
      (node (ref "LED9") (pin "2-DOUT") (pinfunction "DO_2-DOUT") (pintype "output"))
    )
    (net (code "13") (name "Net-(LED10-DO)") (class "Default")
      (node (ref "LED10") (pin "2-DOUT") (pinfunction "DO_2-DOUT") (pintype "output"))
      (node (ref "LED11") (pin "4-DIN") (pinfunction "DI_4-DIN") (pintype "input"))
    )
    (net (code "14") (name "Net-(LED11-DO)") (class "Default")
      (node (ref "LED11") (pin "2-DOUT") (pinfunction "DO_2-DOUT") (pintype "output"))
      (node (ref "LED12") (pin "4-DIN") (pinfunction "DI_4-DIN") (pintype "input"))
    )
    (net (code "15") (name "Net-(LED12-DO)") (class "Default")
      (node (ref "LED12") (pin "2-DOUT") (pinfunction "DO_2-DOUT") (pintype "output"))
      (node (ref "LED13") (pin "4-DIN") (pinfunction "DI_4-DIN") (pintype "input"))
    )
    (net (code "16") (name "Net-(LED13-DO)") (class "Default")
      (node (ref "LED13") (pin "2-DOUT") (pinfunction "DO_2-DOUT") (pintype "output"))
      (node (ref "LED14") (pin "4-DIN") (pinfunction "DI_4-DIN") (pintype "input"))
    )
    (net (code "17") (name "Net-(LED14-DO)") (class "Default")
      (node (ref "LED14") (pin "2-DOUT") (pinfunction "DO_2-DOUT") (pintype "output"))
      (node (ref "LED15") (pin "4-DIN") (pinfunction "DI_4-DIN") (pintype "input"))
    )
    (net (code "18") (name "Net-(LED15-DO)") (class "Default")
      (node (ref "LED15") (pin "2-DOUT") (pinfunction "DO_2-DOUT") (pintype "output"))
      (node (ref "LED16") (pin "4-DIN") (pinfunction "DI_4-DIN") (pintype "input"))
    )
    (net (code "19") (name "Net-(LED16-DO)") (class "Default")
      (node (ref "LED16") (pin "2-DOUT") (pinfunction "DO_2-DOUT") (pintype "output"))
      (node (ref "LED17") (pin "4-DIN") (pinfunction "DI_4-DIN") (pintype "input"))
    )
    (net (code "20") (name "Net-(LED17-DO)") (class "Default")
      (node (ref "LED17") (pin "2-DOUT") (pinfunction "DO_2-DOUT") (pintype "output"))
      (node (ref "LED18") (pin "4-DIN") (pinfunction "DI_4-DIN") (pintype "input"))
    )
    (net (code "21") (name "Net-(LED18-DO)") (class "Default")
      (node (ref "LED18") (pin "2-DOUT") (pinfunction "DO_2-DOUT") (pintype "output"))
      (node (ref "LED19") (pin "4-DIN") (pinfunction "DI_4-DIN") (pintype "input"))
    )
    (net (code "22") (name "Net-(LED19-DO)") (class "Default")
      (node (ref "LED19") (pin "2-DOUT") (pinfunction "DO_2-DOUT") (pintype "output"))
      (node (ref "LED20") (pin "4-DIN") (pinfunction "DI_4-DIN") (pintype "input"))
    )
    (net (code "23") (name "Net-(LED20-DO)") (class "Default")
      (node (ref "LED20") (pin "2-DOUT") (pinfunction "DO_2-DOUT") (pintype "output"))
      (node (ref "LED21") (pin "4-DIN") (pinfunction "DI_4-DIN") (pintype "input"))
    )
    (net (code "24") (name "Net-(LED21-DO)") (class "Default")
      (node (ref "LED21") (pin "2-DOUT") (pinfunction "DO_2-DOUT") (pintype "output"))
      (node (ref "LED22") (pin "4-DIN") (pinfunction "DI_4-DIN") (pintype "input"))
    )
    (net (code "25") (name "Net-(LED22-DO)") (class "Default")
      (node (ref "LED22") (pin "2-DOUT") (pinfunction "DO_2-DOUT") (pintype "output"))
      (node (ref "LED23") (pin "4-DIN") (pinfunction "DI_4-DIN") (pintype "input"))
    )
    (net (code "26") (name "Net-(LED23-DO)") (class "Default")
      (node (ref "LED23") (pin "2-DOUT") (pinfunction "DO_2-DOUT") (pintype "output"))
      (node (ref "LED24") (pin "4-DIN") (pinfunction "DI_4-DIN") (pintype "input"))
    )
    (net (code "27") (name "Net-(LED24-DO)") (class "Default")
      (node (ref "LED24") (pin "2-DOUT") (pinfunction "DO_2-DOUT") (pintype "output"))
      (node (ref "LED25") (pin "4-DIN") (pinfunction "DI_4-DIN") (pintype "input"))
    )
    (net (code "28") (name "Net-(LED25-DO)") (class "Default")
      (node (ref "LED25") (pin "2-DOUT") (pinfunction "DO_2-DOUT") (pintype "output"))
      (node (ref "LED26") (pin "4-DIN") (pinfunction "DI_4-DIN") (pintype "input"))
    )
    (net (code "29") (name "Net-(LED26-DO)") (class "Default")
      (node (ref "LED26") (pin "2-DOUT") (pinfunction "DO_2-DOUT") (pintype "output"))
      (node (ref "LED27") (pin "4-DIN") (pinfunction "DI_4-DIN") (pintype "input"))
    )
    (net (code "30") (name "Net-(LED27-DO)") (class "Default")
      (node (ref "LED27") (pin "2-DOUT") (pinfunction "DO_2-DOUT") (pintype "output"))
      (node (ref "LED28") (pin "4-DIN") (pinfunction "DI_4-DIN") (pintype "input"))
    )
    (net (code "31") (name "Net-(LED28-DO)") (class "Default")
      (node (ref "LED28") (pin "2-DOUT") (pinfunction "DO_2-DOUT") (pintype "output"))
      (node (ref "LED29") (pin "4-DIN") (pinfunction "DI_4-DIN") (pintype "input"))
    )
    (net (code "32") (name "Net-(LED29-DO)") (class "Default")
      (node (ref "LED29") (pin "2-DOUT") (pinfunction "DO_2-DOUT") (pintype "output"))
      (node (ref "LED30") (pin "4-DIN") (pinfunction "DI_4-DIN") (pintype "input"))
    )
    (net (code "33") (name "Net-(LED30-DO)") (class "Default")
      (node (ref "LED30") (pin "2-DOUT") (pinfunction "DO_2-DOUT") (pintype "output"))
      (node (ref "LED31") (pin "4-DIN") (pinfunction "DI_4-DIN") (pintype "input"))
    )
    (net (code "34") (name "Net-(LED31-DO)") (class "Default")
      (node (ref "LED31") (pin "2-DOUT") (pinfunction "DO_2-DOUT") (pintype "output"))
      (node (ref "LED32") (pin "4-DIN") (pinfunction "DI_4-DIN") (pintype "input"))
    )
    (net (code "35") (name "Net-(LED32-DO)") (class "Default")
      (node (ref "LED32") (pin "2-DOUT") (pinfunction "DO_2-DOUT") (pintype "output"))
      (node (ref "LED33") (pin "4-DIN") (pinfunction "DI_4-DIN") (pintype "input"))
    )
    (net (code "36") (name "Net-(LED33-DO)") (class "Default")
      (node (ref "LED33") (pin "2-DOUT") (pinfunction "DO_2-DOUT") (pintype "output"))
      (node (ref "LED34") (pin "4-DIN") (pinfunction "DI_4-DIN") (pintype "input"))
    )
    (net (code "37") (name "Net-(LED34-DO)") (class "Default")
      (node (ref "LED34") (pin "2-DOUT") (pinfunction "DO_2-DOUT") (pintype "output"))
      (node (ref "LED35") (pin "4-DIN") (pinfunction "DI_4-DIN") (pintype "input"))
    )
    (net (code "38") (name "Net-(LED35-DO)") (class "Default")
      (node (ref "LED35") (pin "2-DOUT") (pinfunction "DO_2-DOUT") (pintype "output"))
      (node (ref "LED36") (pin "4-DIN") (pinfunction "DI_4-DIN") (pintype "input"))
    )
    (net (code "39") (name "Net-(LED36-DO)") (class "Default")
      (node (ref "LED36") (pin "2-DOUT") (pinfunction "DO_2-DOUT") (pintype "output"))
      (node (ref "LED37") (pin "4-DIN") (pinfunction "DI_4-DIN") (pintype "input"))
    )
    (net (code "40") (name "Net-(LED37-DO)") (class "Default")
      (node (ref "LED37") (pin "2-DOUT") (pinfunction "DO_2-DOUT") (pintype "output"))
      (node (ref "LED38") (pin "4-DIN") (pinfunction "DI_4-DIN") (pintype "input"))
    )
    (net (code "41") (name "Net-(LED38-DO)") (class "Default")
      (node (ref "LED38") (pin "2-DOUT") (pinfunction "DO_2-DOUT") (pintype "output"))
      (node (ref "LED39") (pin "4-DIN") (pinfunction "DI_4-DIN") (pintype "input"))
    )
    (net (code "42") (name "Net-(LED39-DO)") (class "Default")
      (node (ref "LED39") (pin "2-DOUT") (pinfunction "DO_2-DOUT") (pintype "output"))
      (node (ref "LED40") (pin "4-DIN") (pinfunction "DI_4-DIN") (pintype "input"))
    )
    (net (code "43") (name "Net-(LED40-DO)") (class "Default")
      (node (ref "LED40") (pin "2-DOUT") (pinfunction "DO_2-DOUT") (pintype "output"))
      (node (ref "LED41") (pin "4-DIN") (pinfunction "DI_4-DIN") (pintype "input"))
    )
    (net (code "44") (name "Net-(LED41-DO)") (class "Default")
      (node (ref "LED41") (pin "2-DOUT") (pinfunction "DO_2-DOUT") (pintype "output"))
      (node (ref "LED42") (pin "4-DIN") (pinfunction "DI_4-DIN") (pintype "input"))
    )
    (net (code "45") (name "Net-(LED42-DO)") (class "Default")
      (node (ref "LED42") (pin "2-DOUT") (pinfunction "DO_2-DOUT") (pintype "output"))
      (node (ref "LED43") (pin "4-DIN") (pinfunction "DI_4-DIN") (pintype "input"))
    )
    (net (code "46") (name "Net-(LED43-DO)") (class "Default")
      (node (ref "LED43") (pin "2-DOUT") (pinfunction "DO_2-DOUT") (pintype "output"))
      (node (ref "LED44") (pin "4-DIN") (pinfunction "DI_4-DIN") (pintype "input"))
    )
    (net (code "47") (name "Net-(LED44-DO)") (class "Default")
      (node (ref "LED44") (pin "2-DOUT") (pinfunction "DO_2-DOUT") (pintype "output"))
      (node (ref "LED45") (pin "4-DIN") (pinfunction "DI_4-DIN") (pintype "input"))
    )
    (net (code "48") (name "Net-(LED45-DO)") (class "Default")
      (node (ref "LED45") (pin "2-DOUT") (pinfunction "DO_2-DOUT") (pintype "output"))
      (node (ref "LED46") (pin "4-DIN") (pinfunction "DI_4-DIN") (pintype "input"))
    )
    (net (code "49") (name "Net-(LED46-DO)") (class "Default")
      (node (ref "LED46") (pin "2-DOUT") (pinfunction "DO_2-DOUT") (pintype "output"))
      (node (ref "LED47") (pin "4-DIN") (pinfunction "DI_4-DIN") (pintype "input"))
    )
    (net (code "50") (name "Net-(LED47-DO)") (class "Default")
      (node (ref "LED47") (pin "2-DOUT") (pinfunction "DO_2-DOUT") (pintype "output"))
      (node (ref "LED48") (pin "4-DIN") (pinfunction "DI_4-DIN") (pintype "input"))
    )
    (net (code "51") (name "Net-(LED48-DO)") (class "Default")
      (node (ref "LED48") (pin "2-DOUT") (pinfunction "DO_2-DOUT") (pintype "output"))
      (node (ref "LED49") (pin "4-DIN") (pinfunction "DI_4-DIN") (pintype "input"))
    )
    (net (code "52") (name "Net-(LED49-DO)") (class "Default")
      (node (ref "LED49") (pin "2-DOUT") (pinfunction "DO_2-DOUT") (pintype "output"))
      (node (ref "LED50") (pin "4-DIN") (pinfunction "DI_4-DIN") (pintype "input"))
    )
    (net (code "53") (name "Net-(LED50-DO)") (class "Default")
      (node (ref "LED50") (pin "2-DOUT") (pinfunction "DO_2-DOUT") (pintype "output"))
      (node (ref "LED51") (pin "4-DIN") (pinfunction "DI_4-DIN") (pintype "input"))
    )
    (net (code "54") (name "Net-(LED51-DO)") (class "Default")
      (node (ref "LED51") (pin "2-DOUT") (pinfunction "DO_2-DOUT") (pintype "output"))
      (node (ref "LED52") (pin "4-DIN") (pinfunction "DI_4-DIN") (pintype "input"))
    )
    (net (code "55") (name "Net-(LED52-DO)") (class "Default")
      (node (ref "LED52") (pin "2-DOUT") (pinfunction "DO_2-DOUT") (pintype "output"))
      (node (ref "LED53") (pin "4-DIN") (pinfunction "DI_4-DIN") (pintype "input"))
    )
    (net (code "56") (name "Net-(LED53-DO)") (class "Default")
      (node (ref "LED53") (pin "2-DOUT") (pinfunction "DO_2-DOUT") (pintype "output"))
      (node (ref "LED54") (pin "4-DIN") (pinfunction "DI_4-DIN") (pintype "input"))
    )
    (net (code "57") (name "Net-(LED54-DO)") (class "Default")
      (node (ref "LED54") (pin "2-DOUT") (pinfunction "DO_2-DOUT") (pintype "output"))
      (node (ref "LED55") (pin "4-DIN") (pinfunction "DI_4-DIN") (pintype "input"))
    )
    (net (code "58") (name "Net-(LED55-DO)") (class "Default")
      (node (ref "LED55") (pin "2-DOUT") (pinfunction "DO_2-DOUT") (pintype "output"))
      (node (ref "LED56") (pin "4-DIN") (pinfunction "DI_4-DIN") (pintype "input"))
    )
    (net (code "59") (name "Net-(LED56-DO)") (class "Default")
      (node (ref "LED56") (pin "2-DOUT") (pinfunction "DO_2-DOUT") (pintype "output"))
      (node (ref "LED57") (pin "4-DIN") (pinfunction "DI_4-DIN") (pintype "input"))
    )
    (net (code "60") (name "Net-(LED57-DO)") (class "Default")
      (node (ref "LED57") (pin "2-DOUT") (pinfunction "DO_2-DOUT") (pintype "output"))
      (node (ref "LED58") (pin "4-DIN") (pinfunction "DI_4-DIN") (pintype "input"))
    )
    (net (code "61") (name "Net-(LED58-DO)") (class "Default")
      (node (ref "LED58") (pin "2-DOUT") (pinfunction "DO_2-DOUT") (pintype "output"))
      (node (ref "LED59") (pin "4-DIN") (pinfunction "DI_4-DIN") (pintype "input"))
    )
    (net (code "62") (name "Net-(LED59-DO)") (class "Default")
      (node (ref "LED59") (pin "2-DOUT") (pinfunction "DO_2-DOUT") (pintype "output"))
      (node (ref "LED60") (pin "4-DIN") (pinfunction "DI_4-DIN") (pintype "input"))
    )
    (net (code "63") (name "Net-(LED60-DO)") (class "Default")
      (node (ref "LED60") (pin "2-DOUT") (pinfunction "DO_2-DOUT") (pintype "output"))
      (node (ref "LED61") (pin "4-DIN") (pinfunction "DI_4-DIN") (pintype "input"))
    )
    (net (code "64") (name "VCC") (class "Default")
      (node (ref "C1") (pin "1") (pinfunction "1_1") (pintype "passive"))
      (node (ref "C10") (pin "1") (pinfunction "1_1") (pintype "passive"))
      (node (ref "C11") (pin "1") (pinfunction "1_1") (pintype "passive"))
      (node (ref "C12") (pin "1") (pinfunction "1_1") (pintype "passive"))
      (node (ref "C13") (pin "1") (pinfunction "1_1") (pintype "passive"))
      (node (ref "C14") (pin "1") (pinfunction "1_1") (pintype "passive"))
      (node (ref "C15") (pin "1") (pinfunction "1_1") (pintype "passive"))
      (node (ref "C16") (pin "1") (pinfunction "1_1") (pintype "passive"))
      (node (ref "C17") (pin "1") (pinfunction "1_1") (pintype "passive"))
      (node (ref "C18") (pin "1") (pinfunction "1_1") (pintype "passive"))
      (node (ref "C19") (pin "1") (pinfunction "1_1") (pintype "passive"))
      (node (ref "C2") (pin "1") (pinfunction "1_1") (pintype "passive"))
      (node (ref "C20") (pin "1") (pinfunction "1_1") (pintype "passive"))
      (node (ref "C21") (pin "1") (pinfunction "1_1") (pintype "passive"))
      (node (ref "C22") (pin "1") (pinfunction "1_1") (pintype "passive"))
      (node (ref "C23") (pin "1") (pinfunction "1_1") (pintype "passive"))
      (node (ref "C24") (pin "1") (pinfunction "1_1") (pintype "passive"))
      (node (ref "C25") (pin "1") (pinfunction "1_1") (pintype "passive"))
      (node (ref "C26") (pin "1") (pinfunction "1_1") (pintype "passive"))
      (node (ref "C27") (pin "1") (pinfunction "1_1") (pintype "passive"))
      (node (ref "C28") (pin "1") (pinfunction "1_1") (pintype "passive"))
      (node (ref "C29") (pin "1") (pinfunction "1_1") (pintype "passive"))
      (node (ref "C3") (pin "1") (pinfunction "1_1") (pintype "passive"))
      (node (ref "C30") (pin "1") (pinfunction "1_1") (pintype "passive"))
      (node (ref "C31") (pin "1") (pinfunction "1_1") (pintype "passive"))
      (node (ref "C32") (pin "1") (pinfunction "1_1") (pintype "passive"))
      (node (ref "C33") (pin "1") (pinfunction "1_1") (pintype "passive"))
      (node (ref "C34") (pin "1") (pinfunction "1_1") (pintype "passive"))
      (node (ref "C35") (pin "1") (pinfunction "1_1") (pintype "passive"))
      (node (ref "C36") (pin "1") (pinfunction "1_1") (pintype "passive"))
      (node (ref "C37") (pin "1") (pinfunction "1_1") (pintype "passive"))
      (node (ref "C38") (pin "1") (pinfunction "1_1") (pintype "passive"))
      (node (ref "C39") (pin "1") (pinfunction "1_1") (pintype "passive"))
      (node (ref "C4") (pin "1") (pinfunction "1_1") (pintype "passive"))
      (node (ref "C40") (pin "1") (pinfunction "1_1") (pintype "passive"))
      (node (ref "C41") (pin "1") (pinfunction "1_1") (pintype "passive"))
      (node (ref "C42") (pin "1") (pinfunction "1_1") (pintype "passive"))
      (node (ref "C43") (pin "1") (pinfunction "1_1") (pintype "passive"))
      (node (ref "C44") (pin "1") (pinfunction "1_1") (pintype "passive"))
      (node (ref "C45") (pin "1") (pinfunction "1_1") (pintype "passive"))
      (node (ref "C46") (pin "1") (pinfunction "1_1") (pintype "passive"))
      (node (ref "C47") (pin "1") (pinfunction "1_1") (pintype "passive"))
      (node (ref "C48") (pin "1") (pinfunction "1_1") (pintype "passive"))
      (node (ref "C49") (pin "1") (pinfunction "1_1") (pintype "passive"))
      (node (ref "C5") (pin "1") (pinfunction "1_1") (pintype "passive"))
      (node (ref "C50") (pin "1") (pinfunction "1_1") (pintype "passive"))
      (node (ref "C51") (pin "1") (pinfunction "1_1") (pintype "passive"))
      (node (ref "C52") (pin "1") (pinfunction "1_1") (pintype "passive"))
      (node (ref "C53") (pin "1") (pinfunction "1_1") (pintype "passive"))
      (node (ref "C54") (pin "1") (pinfunction "1_1") (pintype "passive"))
      (node (ref "C55") (pin "1") (pinfunction "1_1") (pintype "passive"))
      (node (ref "C56") (pin "1") (pinfunction "1_1") (pintype "passive"))
      (node (ref "C57") (pin "1") (pinfunction "1_1") (pintype "passive"))
      (node (ref "C58") (pin "1") (pinfunction "1_1") (pintype "passive"))
      (node (ref "C59") (pin "1") (pinfunction "1_1") (pintype "passive"))
      (node (ref "C6") (pin "1") (pinfunction "1_1") (pintype "passive"))
      (node (ref "C60") (pin "1") (pinfunction "1_1") (pintype "passive"))
      (node (ref "C61") (pin "1") (pinfunction "1_1") (pintype "passive"))
      (node (ref "C7") (pin "1") (pinfunction "1_1") (pintype "passive"))
      (node (ref "C8") (pin "1") (pinfunction "1_1") (pintype "passive"))
      (node (ref "C9") (pin "1") (pinfunction "1_1") (pintype "passive"))
      (node (ref "LED1") (pin "1-VDD") (pinfunction "VDD_1-VDD") (pintype "power_in"))
      (node (ref "LED10") (pin "1-VDD") (pinfunction "VDD_1-VDD") (pintype "power_in"))
      (node (ref "LED11") (pin "1-VDD") (pinfunction "VDD_1-VDD") (pintype "power_in"))
      (node (ref "LED12") (pin "1-VDD") (pinfunction "VDD_1-VDD") (pintype "power_in"))
      (node (ref "LED13") (pin "1-VDD") (pinfunction "VDD_1-VDD") (pintype "power_in"))
      (node (ref "LED14") (pin "1-VDD") (pinfunction "VDD_1-VDD") (pintype "power_in"))
      (node (ref "LED15") (pin "1-VDD") (pinfunction "VDD_1-VDD") (pintype "power_in"))
      (node (ref "LED16") (pin "1-VDD") (pinfunction "VDD_1-VDD") (pintype "power_in"))
      (node (ref "LED17") (pin "1-VDD") (pinfunction "VDD_1-VDD") (pintype "power_in"))
      (node (ref "LED18") (pin "1-VDD") (pinfunction "VDD_1-VDD") (pintype "power_in"))
      (node (ref "LED19") (pin "1-VDD") (pinfunction "VDD_1-VDD") (pintype "power_in"))
      (node (ref "LED2") (pin "1-VDD") (pinfunction "VDD_1-VDD") (pintype "power_in"))
      (node (ref "LED20") (pin "1-VDD") (pinfunction "VDD_1-VDD") (pintype "power_in"))
      (node (ref "LED21") (pin "1-VDD") (pinfunction "VDD_1-VDD") (pintype "power_in"))
      (node (ref "LED22") (pin "1-VDD") (pinfunction "VDD_1-VDD") (pintype "power_in"))
      (node (ref "LED23") (pin "1-VDD") (pinfunction "VDD_1-VDD") (pintype "power_in"))
      (node (ref "LED24") (pin "1-VDD") (pinfunction "VDD_1-VDD") (pintype "power_in"))
      (node (ref "LED25") (pin "1-VDD") (pinfunction "VDD_1-VDD") (pintype "power_in"))
      (node (ref "LED26") (pin "1-VDD") (pinfunction "VDD_1-VDD") (pintype "power_in"))
      (node (ref "LED27") (pin "1-VDD") (pinfunction "VDD_1-VDD") (pintype "power_in"))
      (node (ref "LED28") (pin "1-VDD") (pinfunction "VDD_1-VDD") (pintype "power_in"))
      (node (ref "LED29") (pin "1-VDD") (pinfunction "VDD_1-VDD") (pintype "power_in"))
      (node (ref "LED3") (pin "1-VDD") (pinfunction "VDD_1-VDD") (pintype "power_in"))
      (node (ref "LED30") (pin "1-VDD") (pinfunction "VDD_1-VDD") (pintype "power_in"))
      (node (ref "LED31") (pin "1-VDD") (pinfunction "VDD_1-VDD") (pintype "power_in"))
      (node (ref "LED32") (pin "1-VDD") (pinfunction "VDD_1-VDD") (pintype "power_in"))
      (node (ref "LED33") (pin "1-VDD") (pinfunction "VDD_1-VDD") (pintype "power_in"))
      (node (ref "LED34") (pin "1-VDD") (pinfunction "VDD_1-VDD") (pintype "power_in"))
      (node (ref "LED35") (pin "1-VDD") (pinfunction "VDD_1-VDD") (pintype "power_in"))
      (node (ref "LED36") (pin "1-VDD") (pinfunction "VDD_1-VDD") (pintype "power_in"))
      (node (ref "LED37") (pin "1-VDD") (pinfunction "VDD_1-VDD") (pintype "power_in"))
      (node (ref "LED38") (pin "1-VDD") (pinfunction "VDD_1-VDD") (pintype "power_in"))
      (node (ref "LED39") (pin "1-VDD") (pinfunction "VDD_1-VDD") (pintype "power_in"))
      (node (ref "LED4") (pin "1-VDD") (pinfunction "VDD_1-VDD") (pintype "power_in"))
      (node (ref "LED40") (pin "1-VDD") (pinfunction "VDD_1-VDD") (pintype "power_in"))
      (node (ref "LED41") (pin "1-VDD") (pinfunction "VDD_1-VDD") (pintype "power_in"))
      (node (ref "LED42") (pin "1-VDD") (pinfunction "VDD_1-VDD") (pintype "power_in"))
      (node (ref "LED43") (pin "1-VDD") (pinfunction "VDD_1-VDD") (pintype "power_in"))
      (node (ref "LED44") (pin "1-VDD") (pinfunction "VDD_1-VDD") (pintype "power_in"))
      (node (ref "LED45") (pin "1-VDD") (pinfunction "VDD_1-VDD") (pintype "power_in"))
      (node (ref "LED46") (pin "1-VDD") (pinfunction "VDD_1-VDD") (pintype "power_in"))
      (node (ref "LED47") (pin "1-VDD") (pinfunction "VDD_1-VDD") (pintype "power_in"))
      (node (ref "LED48") (pin "1-VDD") (pinfunction "VDD_1-VDD") (pintype "power_in"))
      (node (ref "LED49") (pin "1-VDD") (pinfunction "VDD_1-VDD") (pintype "power_in"))
      (node (ref "LED5") (pin "1-VDD") (pinfunction "VDD_1-VDD") (pintype "power_in"))
      (node (ref "LED50") (pin "1-VDD") (pinfunction "VDD_1-VDD") (pintype "power_in"))
      (node (ref "LED51") (pin "1-VDD") (pinfunction "VDD_1-VDD") (pintype "power_in"))
      (node (ref "LED52") (pin "1-VDD") (pinfunction "VDD_1-VDD") (pintype "power_in"))
      (node (ref "LED53") (pin "1-VDD") (pinfunction "VDD_1-VDD") (pintype "power_in"))
      (node (ref "LED54") (pin "1-VDD") (pinfunction "VDD_1-VDD") (pintype "power_in"))
      (node (ref "LED55") (pin "1-VDD") (pinfunction "VDD_1-VDD") (pintype "power_in"))
      (node (ref "LED56") (pin "1-VDD") (pinfunction "VDD_1-VDD") (pintype "power_in"))
      (node (ref "LED57") (pin "1-VDD") (pinfunction "VDD_1-VDD") (pintype "power_in"))
      (node (ref "LED58") (pin "1-VDD") (pinfunction "VDD_1-VDD") (pintype "power_in"))
      (node (ref "LED59") (pin "1-VDD") (pinfunction "VDD_1-VDD") (pintype "power_in"))
      (node (ref "LED6") (pin "1-VDD") (pinfunction "VDD_1-VDD") (pintype "power_in"))
      (node (ref "LED60") (pin "1-VDD") (pinfunction "VDD_1-VDD") (pintype "power_in"))
      (node (ref "LED61") (pin "1-VDD") (pinfunction "VDD_1-VDD") (pintype "power_in"))
      (node (ref "LED7") (pin "1-VDD") (pinfunction "VDD_1-VDD") (pintype "power_in"))
      (node (ref "LED8") (pin "1-VDD") (pinfunction "VDD_1-VDD") (pintype "power_in"))
      (node (ref "LED9") (pin "1-VDD") (pinfunction "VDD_1-VDD") (pintype "power_in"))
      (node (ref "X1") (pin "2") (pinfunction "S_2") (pintype "passive"))
    )
  )
)
